# Isolator1.net
KiCad netlist of a schematic drawn in EAGLE
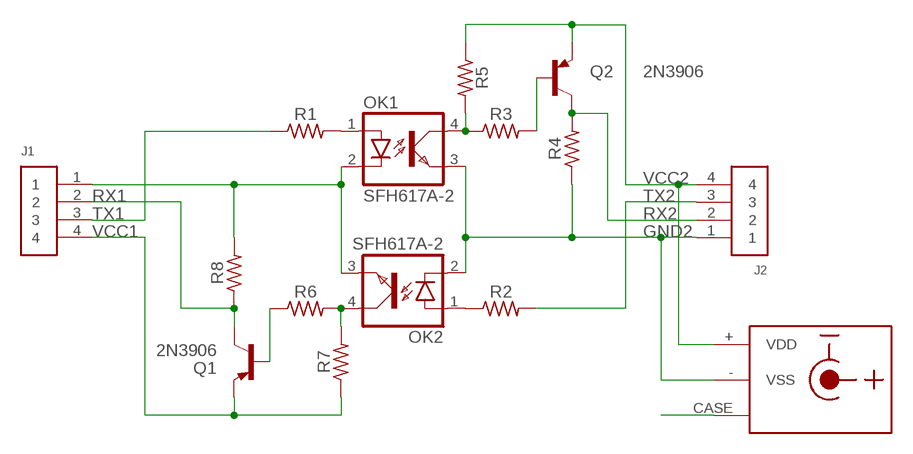
[diagram p0: schematic, sheet 1]

(export (version "E")
  (design (tool "Eeschema 10.0.6"))
  (components
    (comp (ref "J1")
      (value "61300411121")
      (footprint "eagle-import:61300411121")
      (fields
        (field (name "DIGI_KEY_PART_NUMBER") "732-5317-ND")
        (field (name "MANUFACTURER") "Wurth Electronics Inc.")
        (field (name "CREATED_BY") "PCBLayout.com")
      )
      (libsource (lib "eagle-import") (part "61300411121"))
    )
    (comp (ref "J2")
      (value "61300411121")
      (footprint "eagle-import:61300411121")
      (fields
        (field (name "DIGI_KEY_PART_NUMBER") "732-5317-ND")
        (field (name "MANUFACTURER") "Wurth Electronics Inc.")
        (field (name "CREATED_BY") "PCBLayout.com")
      )
      (libsource (lib "eagle-import") (part "61300411121"))
    )
    (comp (ref "OK1")
      (value "SFH617A-2")
      (footprint "eagle-import:DIP4")
      (fields (field (name "MF") "VISHAY/TELEFUNKEN") (field (name "MPN") "SFH618A-2"))
      (libsource (lib "eagle-import") (part "SFH618?A-2"))
    )
    (comp (ref "OK2")
      (value "SFH617A-2")
      (footprint "eagle-import:DIP4")
      (fields (field (name "MF") "VISHAY/TELEFUNKEN") (field (name "MPN") "SFH618A-2"))
      (libsource (lib "eagle-import") (part "SFH618?A-2"))
    )
    (comp (ref "Q1")
      (value "2N3906")
      (footprint "eagle-import:TO92-EBC")
      (libsource (lib "eagle-import") (part "BC557C"))
    )
    (comp (ref "Q2")
      (value "2N3906")
      (footprint "eagle-import:TO92-EBC")
      (libsource (lib "eagle-import") (part "BC557C"))
    )
    (comp (ref "R1")
      (value "200")
      (footprint "eagle-import:0207_7")
      (libsource (lib "eagle-import") (part "R-US_0207/7"))
    )
    (comp (ref "R2")
      (value "200")
      (footprint "eagle-import:0207_7")
      (libsource (lib "eagle-import") (part "R-US_0207/7"))
    )
    (comp (ref "R3")
      (value "1500")
      (footprint "eagle-import:0207_7")
      (libsource (lib "eagle-import") (part "R-US_0207/7"))
    )
    (comp (ref "R4")
      (value "1000")
      (footprint "eagle-import:0207_7")
      (libsource (lib "eagle-import") (part "R-US_0207/7"))
    )
    (comp (ref "R5")
      (value "75")
      (footprint "eagle-import:0207_7")
      (libsource (lib "eagle-import") (part "R-US_0207/7"))
    )
    (comp (ref "R6")
      (value "1500")
      (footprint "eagle-import:0207_7")
      (libsource (lib "eagle-import") (part "R-US_0207/7"))
    )
    (comp (ref "R7")
      (value "75")
      (footprint "eagle-import:0207_7")
      (libsource (lib "eagle-import") (part "R-US_0207/7"))
    )
    (comp (ref "R8")
      (value "1000")
      (footprint "eagle-import:0207_7")
      (libsource (lib "eagle-import") (part "R-US_0207/7"))
    )
    (comp (ref "U$1")
      (value "CUI_PJ-102A")
      (footprint "eagle-import:CUI_DCJACK_PCB")
      (libsource (lib "eagle-import") (part "CUI_PJ-102A"))
    )
  )
  (nets
    (net (code "1") (name "/GND2") (class "Default")
      (node (ref "J2") (pin "1") (pinfunction "1_1") (pintype "passive"))
      (node (ref "OK1") (pin "3") (pinfunction "EMIT_3") (pintype "passive"))
      (node (ref "OK2") (pin "2") (pinfunction "C_2") (pintype "passive"))
      (node (ref "R4") (pin "1") (pinfunction "1_1") (pintype "passive"))
      (node (ref "U$1") (pin "-") (pinfunction "VSS_-") (pintype "power_in"))
    )
    (net (code "2") (name "/RX1") (class "Default")
      (node (ref "J1") (pin "2") (pinfunction "2_2") (pintype "passive"))
      (node (ref "Q1") (pin "C") (pinfunction "C_C") (pintype "passive"))
      (node (ref "R8") (pin "1") (pinfunction "1_1") (pintype "passive"))
    )
    (net (code "3") (name "/RX2") (class "Default")
      (node (ref "J2") (pin "2") (pinfunction "2_2") (pintype "passive"))
      (node (ref "Q2") (pin "C") (pinfunction "C_C") (pintype "passive"))
      (node (ref "R4") (pin "2") (pinfunction "2_2") (pintype "passive"))
    )
    (net (code "4") (name "/TX1") (class "Default")
      (node (ref "J1") (pin "3") (pinfunction "3_3") (pintype "passive"))
      (node (ref "R1") (pin "1") (pinfunction "1_1") (pintype "passive"))
    )
    (net (code "5") (name "/TX2") (class "Default")
      (node (ref "J2") (pin "3") (pinfunction "3_3") (pintype "passive"))
      (node (ref "R2") (pin "2") (pinfunction "2_2") (pintype "passive"))
    )
    (net (code "6") (name "/VCC1") (class "Default")
      (node (ref "J1") (pin "4") (pinfunction "4_4") (pintype "passive"))
      (node (ref "Q1") (pin "E") (pinfunction "E_E") (pintype "passive"))
      (node (ref "R7") (pin "1") (pinfunction "1_1") (pintype "passive"))
    )
    (net (code "7") (name "/VCC2") (class "Default")
      (node (ref "J2") (pin "4") (pinfunction "4_4") (pintype "passive"))
      (node (ref "Q2") (pin "E") (pinfunction "E_E") (pintype "passive"))
      (node (ref "R5") (pin "1") (pinfunction "1_1") (pintype "passive"))
      (node (ref "U$1") (pin "+") (pinfunction "VDD_+") (pintype "power_in"))
    )
    (net (code "8") (name "Net-(OK1-A)") (class "Default")
      (node (ref "OK1") (pin "1") (pinfunction "A_1") (pintype "passive"))
      (node (ref "R1") (pin "2") (pinfunction "2_2") (pintype "passive"))
    )
    (net (code "9") (name "Net-(OK1-C)") (class "Default")
      (node (ref "J1") (pin "1") (pinfunction "1_1") (pintype "passive"))
      (node (ref "OK1") (pin "2") (pinfunction "C_2") (pintype "passive"))
      (node (ref "OK2") (pin "3") (pinfunction "EMIT_3") (pintype "passive"))
      (node (ref "R8") (pin "2") (pinfunction "2_2") (pintype "passive"))
    )
    (net (code "10") (name "Net-(OK1-COL)") (class "Default")
      (node (ref "OK1") (pin "4") (pinfunction "COL_4") (pintype "passive"))
      (node (ref "R3") (pin "1") (pinfunction "1_1") (pintype "passive"))
      (node (ref "R5") (pin "2") (pinfunction "2_2") (pintype "passive"))
    )
    (net (code "11") (name "Net-(OK2-A)") (class "Default")
      (node (ref "OK2") (pin "1") (pinfunction "A_1") (pintype "passive"))
      (node (ref "R2") (pin "1") (pinfunction "1_1") (pintype "passive"))
    )
    (net (code "12") (name "Net-(OK2-COL)") (class "Default")
      (node (ref "OK2") (pin "4") (pinfunction "COL_4") (pintype "passive"))
      (node (ref "R6") (pin "2") (pinfunction "2_2") (pintype "passive"))
      (node (ref "R7") (pin "2") (pinfunction "2_2") (pintype "passive"))
    )
    (net (code "13") (name "Net-(Q1-PadB)") (class "Default")
      (node (ref "Q1") (pin "B") (pinfunction "B_B") (pintype "passive"))
      (node (ref "R6") (pin "1") (pinfunction "1_1") (pintype "passive"))
    )
    (net (code "14") (name "Net-(Q2-PadB)") (class "Default")
      (node (ref "Q2") (pin "B") (pinfunction "B_B") (pintype "passive"))
      (node (ref "R3") (pin "2") (pinfunction "2_2") (pintype "passive"))
    )
    (net (code "15") (name "unconnected-(U$1-PadCASE)") (class "Default")
      (node (ref "U$1") (pin "CASE") (pintype "power_in"))
    )
  )
)
